# FPGA_7A35T_GTP.net
KiCad netlist of a schematic drawn in Altium Designer
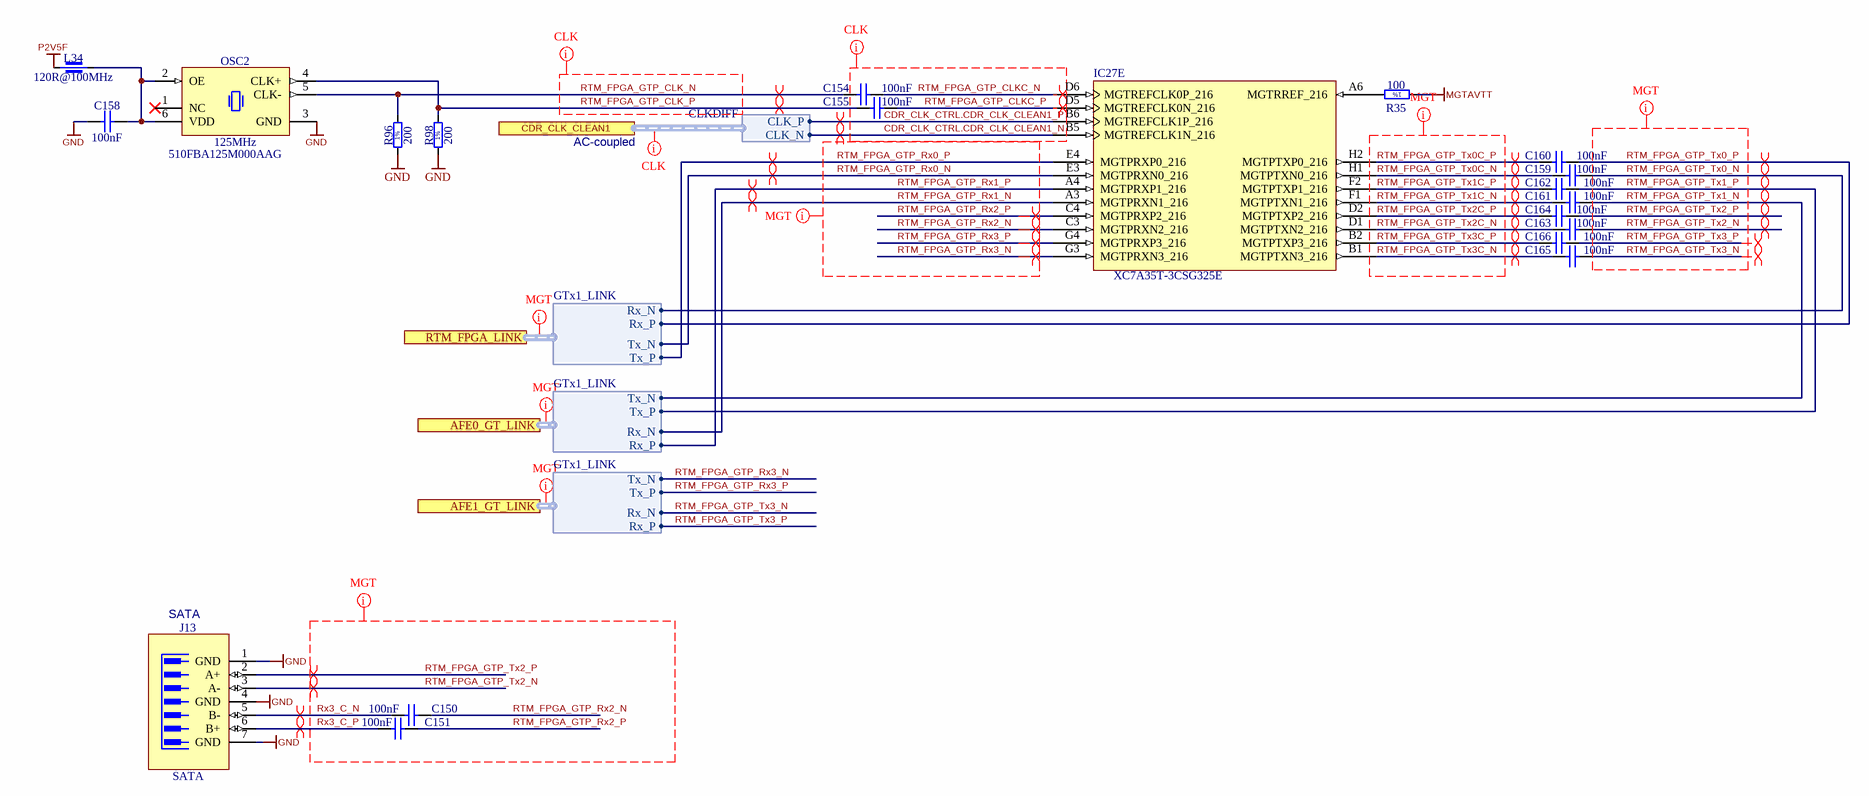
[diagram p0: FPGA_7A35T_GTP.SchDoc]

(export (version "E")
  (design (tool "Eeschema 10.0.6"))
  (components
    (comp (ref "C150")
      (value "100nF")
      (footprint "CAPC0603X33N")
      (description "Non-polarised capacitor")
      (fields
        (field (name "MANUFACTURER PART NUMBER") "CC0201_100NF_6.3V_10%_X5R")
        (field (name "MANUFACTURER") "GENERIC")
        (field (name "AUTHOR") "CERN DEM JLC")
      )
      (libsource (lib "Capacitors") (part "Capacitor - non polarized"))
    )
    (comp (ref "C151")
      (value "100nF")
      (footprint "CAPC0603X33N")
      (description "Non-polarised capacitor")
      (fields
        (field (name "MANUFACTURER PART NUMBER") "CC0201_100NF_6.3V_10%_X5R")
        (field (name "MANUFACTURER") "GENERIC")
        (field (name "AUTHOR") "CERN DEM JLC")
      )
      (libsource (lib "Capacitors") (part "Capacitor - non polarized"))
    )
    (comp (ref "C154")
      (value "100nF")
      (footprint "CAPC0603X33N")
      (description "Non-polarised capacitor")
      (fields
        (field (name "MANUFACTURER PART NUMBER") "CC0201_100NF_6.3V_10%_X5R")
        (field (name "MANUFACTURER") "GENERIC")
        (field (name "AUTHOR") "CERN DEM JLC")
      )
      (libsource (lib "Capacitors") (part "Capacitor - non polarized"))
    )
    (comp (ref "C155")
      (value "100nF")
      (footprint "CAPC0603X33N")
      (description "Non-polarised capacitor")
      (fields
        (field (name "MANUFACTURER PART NUMBER") "CC0201_100NF_6.3V_10%_X5R")
        (field (name "MANUFACTURER") "GENERIC")
        (field (name "AUTHOR") "CERN DEM JLC")
      )
      (libsource (lib "Capacitors") (part "Capacitor - non polarized"))
    )
    (comp (ref "C158")
      (value "100nF")
      (footprint "CAPC0603X33N")
      (description "Non-polarised capacitor")
      (fields
        (field (name "MANUFACTURER PART NUMBER") "CC0201_100NF_6.3V_10%_X5R")
        (field (name "MANUFACTURER") "GENERIC")
        (field (name "AUTHOR") "CERN DEM JLC")
      )
      (libsource (lib "Capacitors") (part "Capacitor - non polarized"))
    )
    (comp (ref "C159")
      (value "100nF")
      (footprint "CAPC0603X33N")
      (description "Non-polarised capacitor")
      (fields
        (field (name "MANUFACTURER PART NUMBER") "CC0201_100NF_6.3V_10%_X5R")
        (field (name "MANUFACTURER") "GENERIC")
        (field (name "AUTHOR") "CERN DEM JLC")
      )
      (libsource (lib "Capacitors") (part "Capacitor - non polarized"))
    )
    (comp (ref "C160")
      (value "100nF")
      (footprint "CAPC0603X33N")
      (description "Non-polarised capacitor")
      (fields
        (field (name "MANUFACTURER PART NUMBER") "CC0201_100NF_6.3V_10%_X5R")
        (field (name "MANUFACTURER") "GENERIC")
        (field (name "AUTHOR") "CERN DEM JLC")
      )
      (libsource (lib "Capacitors") (part "Capacitor - non polarized"))
    )
    (comp (ref "C161")
      (value "100nF")
      (footprint "CAPC0603X33N")
      (description "Non-polarised capacitor")
      (fields
        (field (name "MANUFACTURER PART NUMBER") "CC0201_100NF_6.3V_10%_X5R")
        (field (name "MANUFACTURER") "GENERIC")
        (field (name "AUTHOR") "CERN DEM JLC")
      )
      (libsource (lib "Capacitors") (part "Capacitor - non polarized"))
    )
    (comp (ref "C162")
      (value "100nF")
      (footprint "CAPC0603X33N")
      (description "Non-polarised capacitor")
      (fields
        (field (name "MANUFACTURER PART NUMBER") "CC0201_100NF_6.3V_10%_X5R")
        (field (name "MANUFACTURER") "GENERIC")
        (field (name "AUTHOR") "CERN DEM JLC")
      )
      (libsource (lib "Capacitors") (part "Capacitor - non polarized"))
    )
    (comp (ref "C163")
      (value "100nF")
      (footprint "CAPC0603X33N")
      (description "Non-polarised capacitor")
      (fields
        (field (name "MANUFACTURER PART NUMBER") "CC0201_100NF_6.3V_10%_X5R")
        (field (name "MANUFACTURER") "GENERIC")
        (field (name "AUTHOR") "CERN DEM JLC")
      )
      (libsource (lib "Capacitors") (part "Capacitor - non polarized"))
    )
    (comp (ref "C164")
      (value "100nF")
      (footprint "CAPC0603X33N")
      (description "Non-polarised capacitor")
      (fields
        (field (name "MANUFACTURER PART NUMBER") "CC0201_100NF_6.3V_10%_X5R")
        (field (name "MANUFACTURER") "GENERIC")
        (field (name "AUTHOR") "CERN DEM JLC")
      )
      (libsource (lib "Capacitors") (part "Capacitor - non polarized"))
    )
    (comp (ref "C165")
      (value "100nF")
      (footprint "CAPC0603X33N")
      (description "Non-polarised capacitor")
      (fields
        (field (name "MANUFACTURER PART NUMBER") "CC0201_100NF_6.3V_10%_X5R")
        (field (name "MANUFACTURER") "GENERIC")
        (field (name "AUTHOR") "CERN DEM JLC")
      )
      (libsource (lib "Capacitors") (part "Capacitor - non polarized"))
    )
    (comp (ref "C166")
      (value "100nF")
      (footprint "CAPC0603X33N")
      (description "Non-polarised capacitor")
      (fields
        (field (name "MANUFACTURER PART NUMBER") "CC0201_100NF_6.3V_10%_X5R")
        (field (name "MANUFACTURER") "GENERIC")
        (field (name "AUTHOR") "CERN DEM JLC")
      )
      (libsource (lib "Capacitors") (part "Capacitor - non polarized"))
    )
    (comp (ref "IC27")
      (value "XC7A35T-3CSG325E")
      (footprint "CSG325")
      (description "Artix-7 FPGA, 150 User I/Os, 4 GTP, 324-Ball BGA, Speed Grade 3, Extended Grade, Pb-Free")
      (fields (field (name "MANUFACTURER") "Xilinx"))
      (libsource (lib "Altium Content Vault") (part "XLNX-XC7A35T-CSG325"))
    )
    (comp (ref "J13")
      (value "SATA")
      (footprint "MOLEX_67800-5005")
      (description "7 Pin SATA Receptacle")
      (fields
        (field (name "MANUFACTURER PART NUMBER") "67800-5005")
        (field (name "MANUFACTURER") "MOLEX")
        (field (name "AUTHOR") "CERN DEM MR")
      )
      (libsource (lib "Connectors") (part "Connector SATA 7 Male"))
    )
    (comp (ref "L34")
      (value "120R@100MHz")
      (footprint "INDC1005X55N")
      (fields
        (field (name "MANUFACTURER PART NUMBER") "BLM15PX121SN1D")
        (field (name "MANUFACTURER") "MURATA")
        (field (name "PART NUMBER") "IND0402_MURATA_BLM15PX121SN1D")
        (field (name "AUTHOR") "CERN DEM JMW")
      )
      (libsource (lib "Inductors & Transformers") (part "Ferrite Bead"))
    )
    (comp (ref "OSC2")
      (value "125MHz")
      (footprint "OSC_SILICON-LAB_SI510-6N(5X7)")
      (description "Crystal Oscillator 6 pins, Si510 (LVDS/LVPECL/HCSL/Dual CMOS)")
      (fields
        (field (name "PART NUMBER") "OSC_125MHZ_SILICON-LAB_510FBA125M000AAG")
        (field (name "MANUFACTURER") "SILICON LABS")
        (field (name "MANUFACTURER PART NUMBER") "510FBA125M000AAG")
        (field (name "AUTHOR") "CERN DEM JMW")
      )
      (libsource (lib "ICs And Semiconductors") (part "Oscillator SILICON-LAB_Si510-6N"))
    )
    (comp (ref "R35")
      (value "100")
      (footprint "RESC1005X40N")
      (description "Resistor - 1%")
      (fields
        (field (name "MANUFACTURER PART NUMBER") "R0402_100R_1%_0.0625W_100PPM")
        (field (name "MANUFACTURER") "GENERIC")
        (field (name "AUTHOR") "CERN DEM JLC")
      )
      (libsource (lib "Resistors") (part "Resistor - 1%"))
    )
    (comp (ref "R96")
      (value "200")
      (footprint "RESC1005X40N")
      (description "Resistor - 1%")
      (fields
        (field (name "MANUFACTURER PART NUMBER") "R0402_200R_1%_0.0625W_100PPM")
        (field (name "MANUFACTURER") "GENERIC")
        (field (name "AUTHOR") "CERN DEM JLC")
      )
      (libsource (lib "Resistors") (part "Resistor - 1%"))
    )
    (comp (ref "R98")
      (value "200")
      (footprint "RESC1005X40N")
      (description "Resistor - 1%")
      (fields
        (field (name "MANUFACTURER PART NUMBER") "R0402_200R_1%_0.0625W_100PPM")
        (field (name "MANUFACTURER") "GENERIC")
        (field (name "AUTHOR") "CERN DEM JLC")
      )
      (libsource (lib "Resistors") (part "Resistor - 1%"))
    )
  )
  (nets
    (net (code "3") (name "/CDR_CLK_CTRL.CDR_CLK_CLEAN1_N") (class "Default")
      (node (ref "IC27") (pin "B5") (pinfunction "MGTREFCLK1N_216_B5") (pintype "input"))
    )
    (net (code "4") (name "/CDR_CLK_CTRL.CDR_CLK_CLEAN1_P") (class "Default")
      (node (ref "IC27") (pin "B6") (pinfunction "MGTREFCLK1P_216_B6") (pintype "input"))
    )
    (net (code "5") (name "/RTM_FPGA_GTP_CLKC_N") (class "Default")
      (node (ref "C154") (pin "2") (pinfunction "2_2") (pintype "passive"))
      (node (ref "IC27") (pin "D6") (pinfunction "MGTREFCLK0P_216_D6") (pintype "input"))
    )
    (net (code "6") (name "/RTM_FPGA_GTP_CLKC_P") (class "Default")
      (node (ref "C155") (pin "2") (pinfunction "2_2") (pintype "passive"))
      (node (ref "IC27") (pin "D5") (pinfunction "MGTREFCLK0N_216_D5") (pintype "input"))
    )
    (net (code "7") (name "/RTM_FPGA_GTP_CLK_N") (class "Default")
      (node (ref "C154") (pin "1") (pinfunction "1_1") (pintype "passive"))
      (node (ref "OSC2") (pin "5") (pinfunction "CLK-_5") (pintype "output"))
      (node (ref "R96") (pin "2") (pinfunction "2_2") (pintype "passive"))
    )
    (net (code "8") (name "/RTM_FPGA_GTP_CLK_P") (class "Default")
      (node (ref "C155") (pin "1") (pinfunction "1_1") (pintype "passive"))
      (node (ref "OSC2") (pin "4") (pinfunction "CLK+_4") (pintype "output"))
      (node (ref "R98") (pin "2") (pinfunction "2_2") (pintype "passive"))
    )
    (net (code "9") (name "/RTM_FPGA_GTP_Rx0_N") (class "Default")
      (node (ref "IC27") (pin "E3") (pinfunction "MGTPRXN0_216_E3") (pintype "input"))
    )
    (net (code "10") (name "/RTM_FPGA_GTP_Rx0_P") (class "Default")
      (node (ref "IC27") (pin "E4") (pinfunction "MGTPRXP0_216_E4") (pintype "input"))
    )
    (net (code "11") (name "/RTM_FPGA_GTP_Rx1_N") (class "Default")
      (node (ref "IC27") (pin "A3") (pinfunction "MGTPRXN1_216_A3") (pintype "input"))
    )
    (net (code "12") (name "/RTM_FPGA_GTP_Rx1_P") (class "Default")
      (node (ref "IC27") (pin "A4") (pinfunction "MGTPRXP1_216_A4") (pintype "input"))
    )
    (net (code "13") (name "/RTM_FPGA_GTP_Rx2_N") (class "Default")
      (node (ref "C150") (pin "2") (pinfunction "2_2") (pintype "passive"))
      (node (ref "IC27") (pin "C3") (pinfunction "MGTPRXN2_216_C3") (pintype "input"))
    )
    (net (code "14") (name "/RTM_FPGA_GTP_Rx2_P") (class "Default")
      (node (ref "C151") (pin "2") (pinfunction "2_2") (pintype "passive"))
      (node (ref "IC27") (pin "C4") (pinfunction "MGTPRXP2_216_C4") (pintype "input"))
    )
    (net (code "15") (name "/RTM_FPGA_GTP_Rx3_N") (class "Default")
      (node (ref "IC27") (pin "G3") (pinfunction "MGTPRXN3_216_G3") (pintype "input"))
    )
    (net (code "16") (name "/RTM_FPGA_GTP_Rx3_P") (class "Default")
      (node (ref "IC27") (pin "G4") (pinfunction "MGTPRXP3_216_G4") (pintype "input"))
    )
    (net (code "17") (name "/RTM_FPGA_GTP_Tx0C_N") (class "Default")
      (node (ref "C159") (pin "2") (pinfunction "2_2") (pintype "passive"))
      (node (ref "IC27") (pin "H1") (pinfunction "MGTPTXN0_216_H1") (pintype "output"))
    )
    (net (code "18") (name "/RTM_FPGA_GTP_Tx0C_P") (class "Default")
      (node (ref "C160") (pin "2") (pinfunction "2_2") (pintype "passive"))
      (node (ref "IC27") (pin "H2") (pinfunction "MGTPTXP0_216_H2") (pintype "output"))
    )
    (net (code "19") (name "/RTM_FPGA_GTP_Tx0_N") (class "Default")
      (node (ref "C159") (pin "1") (pinfunction "1_1") (pintype "passive"))
    )
    (net (code "20") (name "/RTM_FPGA_GTP_Tx0_P") (class "Default")
      (node (ref "C160") (pin "1") (pinfunction "1_1") (pintype "passive"))
    )
    (net (code "21") (name "/RTM_FPGA_GTP_Tx1C_N") (class "Default")
      (node (ref "C161") (pin "2") (pinfunction "2_2") (pintype "passive"))
      (node (ref "IC27") (pin "F1") (pinfunction "MGTPTXN1_216_F1") (pintype "output"))
    )
    (net (code "22") (name "/RTM_FPGA_GTP_Tx1C_P") (class "Default")
      (node (ref "C162") (pin "2") (pinfunction "2_2") (pintype "passive"))
      (node (ref "IC27") (pin "F2") (pinfunction "MGTPTXP1_216_F2") (pintype "output"))
    )
    (net (code "23") (name "/RTM_FPGA_GTP_Tx1_N") (class "Default")
      (node (ref "C161") (pin "1") (pinfunction "1_1") (pintype "passive"))
    )
    (net (code "24") (name "/RTM_FPGA_GTP_Tx1_P") (class "Default")
      (node (ref "C162") (pin "1") (pinfunction "1_1") (pintype "passive"))
    )
    (net (code "25") (name "/RTM_FPGA_GTP_Tx2C_N") (class "Default")
      (node (ref "C163") (pin "2") (pinfunction "2_2") (pintype "passive"))
      (node (ref "IC27") (pin "D1") (pinfunction "MGTPTXN2_216_D1") (pintype "output"))
    )
    (net (code "26") (name "/RTM_FPGA_GTP_Tx2C_P") (class "Default")
      (node (ref "C164") (pin "2") (pinfunction "2_2") (pintype "passive"))
      (node (ref "IC27") (pin "D2") (pinfunction "MGTPTXP2_216_D2") (pintype "output"))
    )
    (net (code "27") (name "/RTM_FPGA_GTP_Tx2_N") (class "Default")
      (node (ref "C163") (pin "1") (pinfunction "1_1") (pintype "passive"))
      (node (ref "J13") (pin "3") (pinfunction "A-_3") (pintype "bidirectional"))
    )
    (net (code "28") (name "/RTM_FPGA_GTP_Tx2_P") (class "Default")
      (node (ref "C164") (pin "1") (pinfunction "1_1") (pintype "passive"))
      (node (ref "J13") (pin "2") (pinfunction "A+_2") (pintype "bidirectional"))
    )
    (net (code "29") (name "/RTM_FPGA_GTP_Tx3C_N") (class "Default")
      (node (ref "C165") (pin "2") (pinfunction "2_2") (pintype "passive"))
      (node (ref "IC27") (pin "B1") (pinfunction "MGTPTXN3_216_B1") (pintype "output"))
    )
    (net (code "30") (name "/RTM_FPGA_GTP_Tx3C_P") (class "Default")
      (node (ref "C166") (pin "2") (pinfunction "2_2") (pintype "passive"))
      (node (ref "IC27") (pin "B2") (pinfunction "MGTPTXP3_216_B2") (pintype "output"))
    )
    (net (code "31") (name "/RTM_FPGA_GTP_Tx3_N") (class "Default")
      (node (ref "C165") (pin "1") (pinfunction "1_1") (pintype "passive"))
    )
    (net (code "32") (name "/RTM_FPGA_GTP_Tx3_P") (class "Default")
      (node (ref "C166") (pin "1") (pinfunction "1_1") (pintype "passive"))
    )
    (net (code "33") (name "/Rx3_C_N") (class "Default")
      (node (ref "C150") (pin "1") (pinfunction "1_1") (pintype "passive"))
      (node (ref "J13") (pin "5") (pinfunction "B-_5") (pintype "bidirectional"))
    )
    (net (code "34") (name "/Rx3_C_P") (class "Default")
      (node (ref "C151") (pin "1") (pinfunction "1_1") (pintype "passive"))
      (node (ref "J13") (pin "6") (pinfunction "B+_6") (pintype "bidirectional"))
    )
    (net (code "37") (name "GND") (class "Default")
      (node (ref "C158") (pin "1") (pinfunction "1_1") (pintype "passive"))
      (node (ref "J13") (pin "1") (pinfunction "GND_1") (pintype "power_in"))
      (node (ref "J13") (pin "4") (pinfunction "GND_4") (pintype "power_in"))
      (node (ref "J13") (pin "7") (pinfunction "GND_7") (pintype "power_in"))
      (node (ref "OSC2") (pin "3") (pinfunction "GND_3") (pintype "power_in"))
      (node (ref "R96") (pin "1") (pinfunction "1_1") (pintype "passive"))
      (node (ref "R98") (pin "1") (pinfunction "1_1") (pintype "passive"))
    )
    (net (code "38") (name "MGTAVTT") (class "Default")
      (node (ref "R35") (pin "1") (pinfunction "1_1") (pintype "passive"))
    )
    (net (code "39") (name "Net-(IC27E-MGTRREF_216)") (class "Default")
      (node (ref "IC27") (pin "A6") (pinfunction "MGTRREF_216_A6") (pintype "input"))
      (node (ref "R35") (pin "2") (pinfunction "2_2") (pintype "passive"))
    )
    (net (code "40") (name "Net-(OSC2-OE)") (class "Default")
      (node (ref "C158") (pin "2") (pinfunction "2_2") (pintype "passive"))
      (node (ref "L34") (pin "1") (pinfunction "1_1") (pintype "passive"))
      (node (ref "OSC2") (pin "2") (pinfunction "OE_2") (pintype "input"))
      (node (ref "OSC2") (pin "6") (pinfunction "VDD_6") (pintype "power_in"))
    )
    (net (code "41") (name "P2V5F") (class "Default")
      (node (ref "L34") (pin "2") (pinfunction "2_2") (pintype "passive"))
    )
    (net (code "42") (name "unconnected-(OSC2-NC-Pad1)") (class "Default")
      (node (ref "OSC2") (pin "1") (pinfunction "NC_1") (pintype "passive+no_connect"))
    )
  )
)
